# SCREEN.net
KiCad netlist of a schematic drawn in Altium Designer
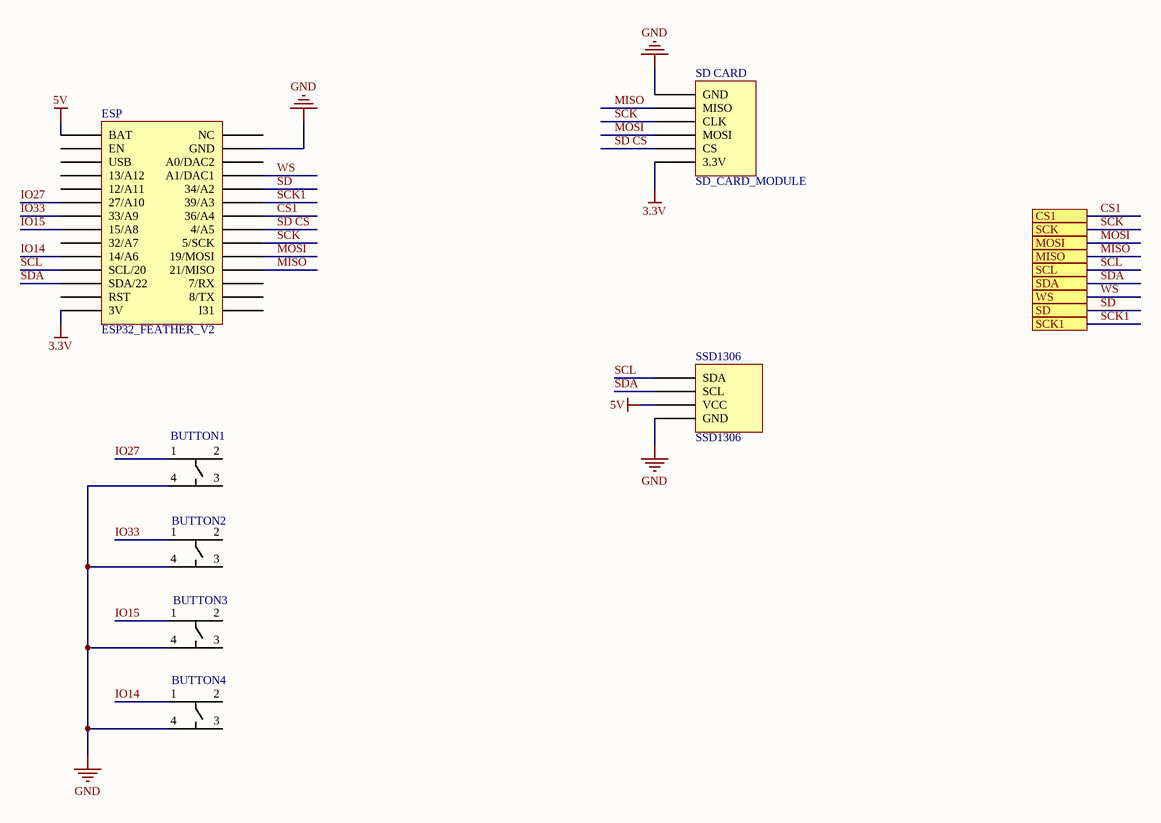
[diagram p0: SCREEN.SchDoc]

(export (version "E")
  (design (tool "Eeschema 10.0.6"))
  (components
    (comp (ref "BUTTON1")
      (value "BUTTON")
      (footprint "BUTTON 4PIN")
      (description "6X6X5mm")
      (libsource (lib "KHOEMACH_LIB") (part "BUTTON"))
    )
    (comp (ref "BUTTON2")
      (value "BUTTON")
      (footprint "BUTTON 4PIN")
      (description "6X6X5mm")
      (libsource (lib "KHOEMACH_LIB") (part "BUTTON"))
    )
    (comp (ref "BUTTON3")
      (value "BUTTON")
      (footprint "BUTTON 4PIN")
      (description "6X6X5mm")
      (libsource (lib "KHOEMACH_LIB") (part "BUTTON"))
    )
    (comp (ref "BUTTON4")
      (value "BUTTON")
      (footprint "BUTTON 4PIN")
      (description "6X6X5mm")
      (libsource (lib "KHOEMACH_LIB") (part "BUTTON"))
    )
    (comp (ref "ESP")
      (value "ESP32_FEATHER_V2")
      (footprint "ESP32_FEATHER_V2")
      (description "ESP32 Feather V2")
      (libsource (lib "KHOEMACH_LIB") (part "ESP32_FEATHER_V2"))
    )
    (comp (ref "SD CARD")
      (value "SD_CARD_MODULE")
      (footprint "MICRO_SD_CARD_MODULE")
      (libsource (lib "KHOEMACH_LIB") (part "SD_CARD_MODULE"))
    )
    (comp (ref "SSD1306")
      (value "SSD1306")
      (footprint "SSD1306")
      (description "0.96 inch, 128x64")
      (libsource (lib "KHOEMACH_LIB") (part "SSD1306"))
    )
  )
  (nets
    (net (code "1") (name "/CS1") (class "Default")
      (node (ref "ESP") (pin "8") (pinfunction "36/A4_8") (pintype "passive"))
    )
    (net (code "2") (name "/IO14") (class "Default")
      (node (ref "BUTTON4") (pin "1") (pinfunction "1_1") (pintype "passive"))
      (node (ref "ESP") (pin "26") (pinfunction "14/A6_26") (pintype "passive"))
    )
    (net (code "3") (name "/IO15") (class "Default")
      (node (ref "BUTTON3") (pin "1") (pinfunction "1_1") (pintype "passive"))
      (node (ref "ESP") (pin "24") (pinfunction "15/A8_24") (pintype "passive"))
    )
    (net (code "4") (name "/IO27") (class "Default")
      (node (ref "BUTTON1") (pin "1") (pinfunction "1_1") (pintype "passive"))
      (node (ref "ESP") (pin "22") (pinfunction "27/A10_22") (pintype "passive"))
    )
    (net (code "5") (name "/IO33") (class "Default")
      (node (ref "BUTTON2") (pin "1") (pinfunction "1_1") (pintype "passive"))
      (node (ref "ESP") (pin "23") (pinfunction "33/A9_23") (pintype "passive"))
    )
    (net (code "6") (name "/MISO") (class "Default")
      (node (ref "ESP") (pin "4") (pinfunction "21/MISO_4") (pintype "passive"))
      (node (ref "SD CARD") (pin "2") (pinfunction "MISO_2") (pintype "passive"))
    )
    (net (code "7") (name "/MOSI") (class "Default")
      (node (ref "ESP") (pin "5") (pinfunction "19/MOSI_5") (pintype "passive"))
      (node (ref "SD CARD") (pin "4") (pinfunction "MOSI_4") (pintype "passive"))
    )
    (net (code "8") (name "/SCK") (class "Default")
      (node (ref "ESP") (pin "6") (pinfunction "5/SCK_6") (pintype "passive"))
      (node (ref "SD CARD") (pin "3") (pinfunction "CLK_3") (pintype "passive"))
    )
    (net (code "9") (name "/SCK1") (class "Default")
      (node (ref "ESP") (pin "9") (pinfunction "39/A3_9") (pintype "passive"))
    )
    (net (code "10") (name "/SCL") (class "Default")
      (node (ref "ESP") (pin "27") (pinfunction "SCL/20_27") (pintype "passive"))
      (node (ref "SSD1306") (pin "1") (pinfunction "SDA_1") (pintype "passive"))
    )
    (net (code "11") (name "/SD") (class "Default")
      (node (ref "ESP") (pin "10") (pinfunction "34/A2_10") (pintype "passive"))
    )
    (net (code "12") (name "/SD CS") (class "Default")
      (node (ref "ESP") (pin "7") (pinfunction "4/A5_7") (pintype "passive"))
      (node (ref "SD CARD") (pin "5") (pinfunction "CS_5") (pintype "passive"))
    )
    (net (code "13") (name "/SDA") (class "Default")
      (node (ref "ESP") (pin "28") (pinfunction "SDA/22_28") (pintype "passive"))
      (node (ref "SSD1306") (pin "2") (pinfunction "SCL_2") (pintype "passive"))
    )
    (net (code "14") (name "/WS") (class "Default")
      (node (ref "ESP") (pin "11") (pinfunction "A1/DAC1_11") (pintype "passive"))
    )
    (net (code "15") (name "3.3V") (class "Default")
      (node (ref "ESP") (pin "15") (pinfunction "3V_15") (pintype "passive"))
      (node (ref "SD CARD") (pin "6") (pinfunction "3.3V_6") (pintype "passive"))
    )
    (net (code "16") (name "5V") (class "Default")
      (node (ref "ESP") (pin "17") (pinfunction "BAT_17") (pintype "passive"))
      (node (ref "SSD1306") (pin "3") (pinfunction "VCC_3") (pintype "passive"))
    )
    (net (code "17") (name "GND") (class "Default")
      (node (ref "BUTTON1") (pin "4") (pinfunction "4_4") (pintype "passive"))
      (node (ref "BUTTON2") (pin "4") (pinfunction "4_4") (pintype "passive"))
      (node (ref "BUTTON3") (pin "4") (pinfunction "4_4") (pintype "passive"))
      (node (ref "BUTTON4") (pin "4") (pinfunction "4_4") (pintype "passive"))
      (node (ref "ESP") (pin "13") (pinfunction "GND_13") (pintype "passive"))
      (node (ref "SD CARD") (pin "1") (pinfunction "GND_1") (pintype "passive"))
      (node (ref "SSD1306") (pin "4") (pinfunction "GND_4") (pintype "passive"))
    )
    (net (code "18") (name "unconnected-(BUTTON1-Pad2)") (class "Default")
      (node (ref "BUTTON1") (pin "2") (pinfunction "2_2") (pintype "passive"))
    )
    (net (code "19") (name "unconnected-(BUTTON1-Pad3)") (class "Default")
      (node (ref "BUTTON1") (pin "3") (pinfunction "3_3") (pintype "passive"))
    )
    (net (code "20") (name "unconnected-(BUTTON2-Pad2)") (class "Default")
      (node (ref "BUTTON2") (pin "2") (pinfunction "2_2") (pintype "passive"))
    )
    (net (code "21") (name "unconnected-(BUTTON2-Pad3)") (class "Default")
      (node (ref "BUTTON2") (pin "3") (pinfunction "3_3") (pintype "passive"))
    )
    (net (code "22") (name "unconnected-(BUTTON3-Pad2)") (class "Default")
      (node (ref "BUTTON3") (pin "2") (pinfunction "2_2") (pintype "passive"))
    )
    (net (code "23") (name "unconnected-(BUTTON3-Pad3)") (class "Default")
      (node (ref "BUTTON3") (pin "3") (pinfunction "3_3") (pintype "passive"))
    )
    (net (code "24") (name "unconnected-(BUTTON4-Pad2)") (class "Default")
      (node (ref "BUTTON4") (pin "2") (pinfunction "2_2") (pintype "passive"))
    )
    (net (code "25") (name "unconnected-(BUTTON4-Pad3)") (class "Default")
      (node (ref "BUTTON4") (pin "3") (pinfunction "3_3") (pintype "passive"))
    )
    (net (code "26") (name "unconnected-(ESP-7{slash}RX-Pad3)") (class "Default")
      (node (ref "ESP") (pin "3") (pinfunction "7/RX_3") (pintype "passive"))
    )
    (net (code "27") (name "unconnected-(ESP-8{slash}TX-Pad2)") (class "Default")
      (node (ref "ESP") (pin "2") (pinfunction "8/TX_2") (pintype "passive"))
    )
    (net (code "28") (name "unconnected-(ESP-12{slash}A11-Pad21)") (class "Default")
      (node (ref "ESP") (pin "21") (pinfunction "12/A11_21") (pintype "passive"))
    )
    (net (code "29") (name "unconnected-(ESP-13{slash}A12-Pad20)") (class "Default")
      (node (ref "ESP") (pin "20") (pinfunction "13/A12_20") (pintype "passive"))
    )
    (net (code "30") (name "unconnected-(ESP-32{slash}A7-Pad25)") (class "Default")
      (node (ref "ESP") (pin "25") (pinfunction "32/A7_25") (pintype "passive"))
    )
    (net (code "31") (name "unconnected-(ESP-A0{slash}DAC2-Pad12)") (class "Default")
      (node (ref "ESP") (pin "12") (pinfunction "A0/DAC2_12") (pintype "passive"))
    )
    (net (code "32") (name "unconnected-(ESP-EN-Pad18)") (class "Default")
      (node (ref "ESP") (pin "18") (pinfunction "EN_18") (pintype "passive"))
    )
    (net (code "33") (name "unconnected-(ESP-I31-Pad1)") (class "Default")
      (node (ref "ESP") (pin "1") (pinfunction "I31_1") (pintype "passive"))
    )
    (net (code "34") (name "unconnected-(ESP-NC-Pad14)") (class "Default")
      (node (ref "ESP") (pin "14") (pinfunction "NC_14") (pintype "passive"))
    )
    (net (code "35") (name "unconnected-(ESP-RST-Pad16)") (class "Default")
      (node (ref "ESP") (pin "16") (pinfunction "RST_16") (pintype "passive"))
    )
    (net (code "36") (name "unconnected-(ESP-USB-Pad19)") (class "Default")
      (node (ref "ESP") (pin "19") (pinfunction "USB_19") (pintype "passive"))
    )
  )
)
